# DIB_Top_Sheet.net
KiCad netlist of a schematic drawn in Altium Designer
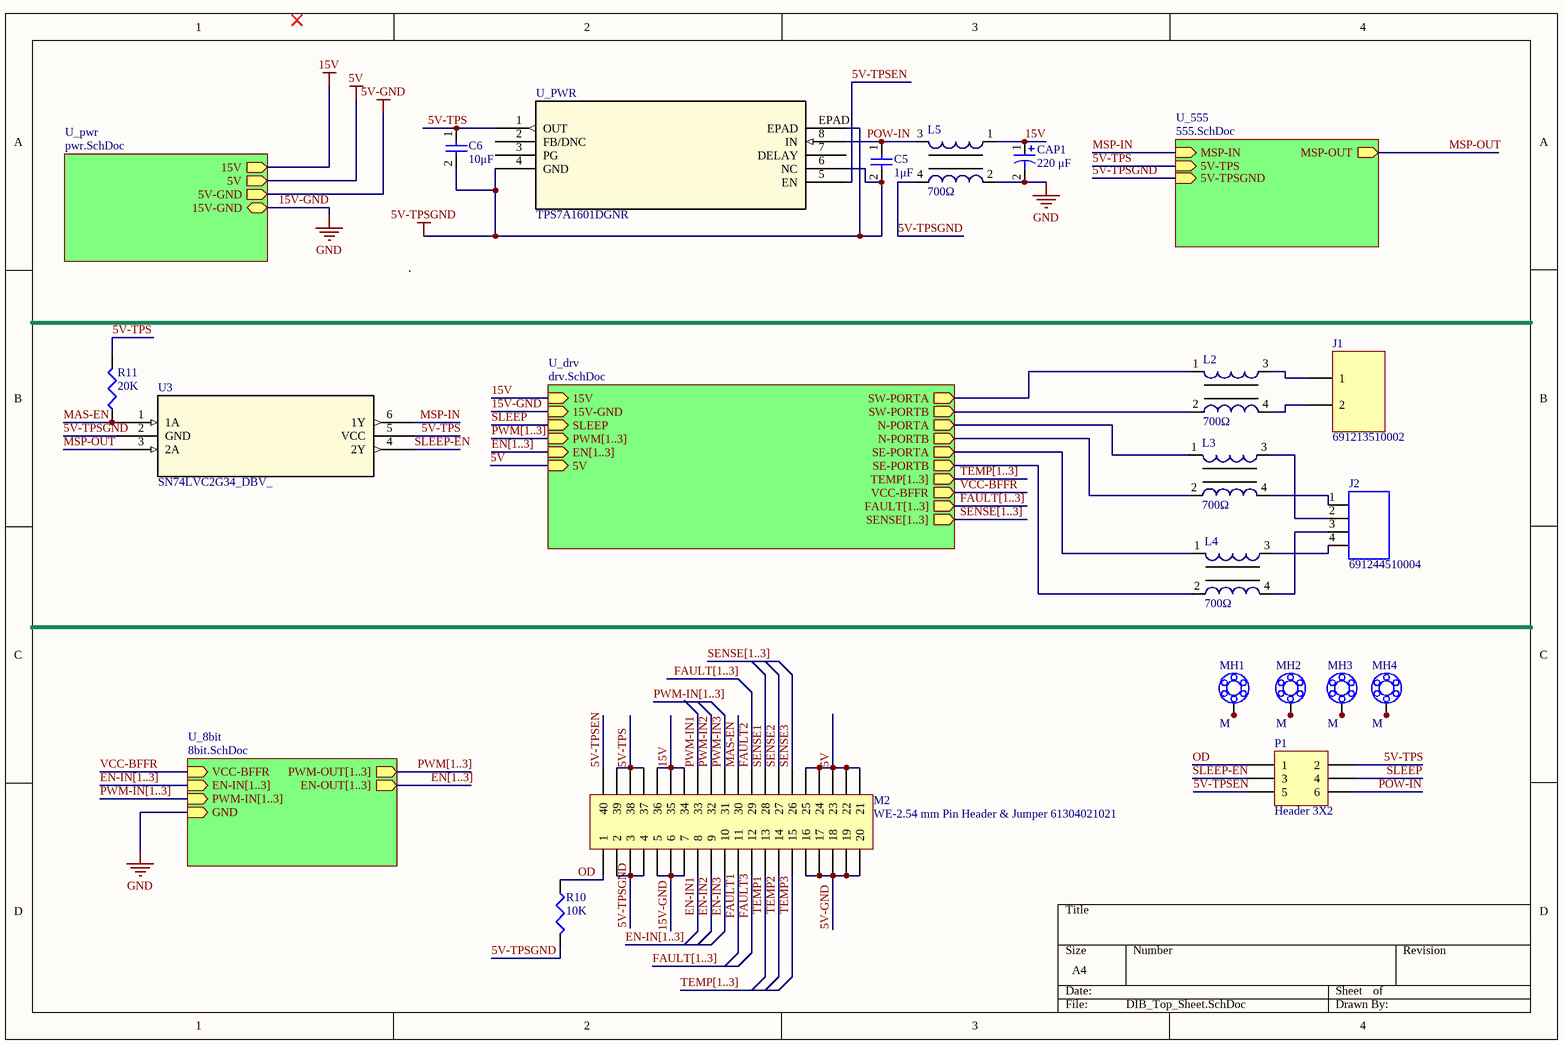
[diagram p0: DIB_Top_Sheet.SchDoc]

(export (version "E")
  (design (tool "Eeschema 10.0.6"))
  (components
    (comp (ref "C5")
      (value "1μF")
      (footprint "WCAP-CSGP 0805, H=1.25mm")
      (description "CAP CER 1UF 50V 10% X5R 0805")
      (fields
        (field (name "MANUFACTURER") "TDK")
        (field (name "PARTNO") "CGA4J3X5R1H105K125AB (C6)")
        (field (name "CREATED BY") "Saurabh")
      )
      (libsource (lib "WCAP-CSGP_rev15b") (part "WCAP-CSGP 0805, 885012207026"))
    )
    (comp (ref "C6")
      (value "10μF")
      (footprint "WCAP-CSGP 0805, H=1.25mm")
      (description "CAP CER 10UF 6.3V 10% X7R 0805")
      (fields
        (field (name "MANUFACTURER") "TDK")
        (field (name "PARTNO") "CGJ4J1X7R0J106K125AC")
        (field (name "CREATED BY") "Saurabh")
      )
      (libsource (lib "WCAP-CSGP_rev15b") (part "WCAP-CSGP 0805, 885012207026"))
    )
    (comp (ref "CAP1")
      (value "220 μF")
      (footprint "WCAP-ASLL 10x10.5x4.5")
      (description "WCAP-ASLL Aluminum Electrolytic Capacitors , 220 μF; + / - 20%; 35 V , 10 x 10,5")
      (fields
        (field (name "MANUFACTURER") "Wurth Elektronik")
        (field (name "PARTNO") "865060557008")
        (field (name "E-MAIL") "libraries@we-online.com")
        (field (name "CREATED BY") "Karrer Zheng")
      )
      (libsource (lib "WCAP-ASLL_rev15a") (part "WCAP-ASLL 10x10.5x4.5 865060557008"))
    )
    (comp (ref "J1")
      (value "691213510002")
      (footprint "691213510002")
      (description "Horizontal Cable Entry with Rising Cage Clamp, Serie 2135 - 5.08 mm")
      (fields (field (name "MANUFACTURER") "Wurth Elektronik") (field (name "CREATED BY") "Baojun Chen"))
      (libsource (lib "WE_WR-TBL_Rising Cage System_5.08 mm_rev15b") (part "691213510002"))
    )
    (comp (ref "J2")
      (value "691244510004")
      (footprint "691244510004")
      (description "WR-TBL Horizontal Cable Entry With Rising Cage Clamp,Serie 2445 - 5.08 mm")
      (fields (field (name "MANUFACTURER") "Wurth Elektronik") (field (name "CREATED BY") "Baojun Chen"))
      (libsource (lib "WE_WR-TBL_Rising Cage System_5.08 mm_rev15b") (part "691244510004"))
    )
    (comp (ref "L2")
      (value "700Ω")
      (footprint "IND_TDK_ACM70600")
      (description "ACM7060-701-2PL-TL01")
      (fields (field (name "MANUFACTURER") "TDK") (field (name "CREATED BY") "Saurabh Sharma"))
      (libsource (lib "WE-SCC_rev15a") (part "WE-SCC 7345, 744281100"))
    )
    (comp (ref "L3")
      (value "700Ω")
      (footprint "IND_TDK_ACM70600")
      (description "ACM7060-701-2PL-TL01")
      (fields (field (name "MANUFACTURER") "TDK") (field (name "CREATED BY") "Saurabh Sharma"))
      (libsource (lib "WE-SCC_rev15a") (part "WE-SCC 7345, 744281100"))
    )
    (comp (ref "L4")
      (value "700Ω")
      (footprint "IND_TDK_ACM70600")
      (description "ACM7060-701-2PL-TL01")
      (fields (field (name "MANUFACTURER") "TDK") (field (name "CREATED BY") "Saurabh Sharma"))
      (libsource (lib "WE-SCC_rev15a") (part "WE-SCC 7345, 744281100"))
    )
    (comp (ref "L5")
      (value "700Ω")
      (footprint "IND_TDK_ACM70600")
      (description "ACM7060-701-2PL-TL01")
      (fields (field (name "MANUFACTURER") "TDK") (field (name "CREATED BY") "Saurabh Sharma"))
      (libsource (lib "") (part "WE-SCC 7345, 744281100_1"))
    )
    (comp (ref "M2")
      (value "WE-2.54 mm Pin Header & Jumper 61304021021")
      (footprint "61304021021")
      (description "WR-PHD 2.54 mm Angled Dual Pin Header")
      (fields
        (field (name "MANUFACTURER") "Würth Elektronik eiSos GmbH")
        (field (name "PARTNO") "61304021021")
        (field (name "CREATED BY") "Karrer Zheng")
      )
      (libsource (lib "WE_WR-PHD_Pin Header_2.54mm_rev15c") (part "WE-2.54 mm Pin Header & Jumper 61304021021"))
    )
    (comp (ref "MH1")
      (value "M")
      (footprint "MOUNTING")
      (description "MOUNTING HOLE - NON INSTALLABLE")
      (libsource (lib "vh_altium_library") (part "MOUNTING"))
    )
    (comp (ref "MH2")
      (value "M")
      (footprint "MOUNTING")
      (description "MOUNTING HOLE - NON INSTALLABLE")
      (libsource (lib "vh_altium_library") (part "MOUNTING"))
    )
    (comp (ref "MH3")
      (value "M")
      (footprint "MOUNTING")
      (description "MOUNTING HOLE - NON INSTALLABLE")
      (libsource (lib "vh_altium_library") (part "MOUNTING"))
    )
    (comp (ref "MH4")
      (value "M")
      (footprint "MOUNTING")
      (description "MOUNTING HOLE - NON INSTALLABLE")
      (libsource (lib "vh_altium_library") (part "MOUNTING"))
    )
    (comp (ref "P1")
      (value "Header 3X2")
      (footprint "HDR2X3")
      (description "Header, 3-Pin, Dual row")
      (fields (field (name "PUBLISHER") "Altium Limited"))
      (libsource (lib "Miscellaneous Connectors") (part "Header 3X2"))
    )
    (comp (ref "R10")
      (value "10K")
      (footprint "J1-0603")
      (description "Resistor")
      (fields (field (name "PUBLISHER") "Altium Limited"))
      (libsource (lib "Miscellaneous Devices") (part "Res3"))
    )
    (comp (ref "R11")
      (value "20K")
      (footprint "J1-0603")
      (description "Resistor")
      (fields (field (name "PUBLISHER") "Altium Limited"))
      (libsource (lib "Miscellaneous Devices") (part "Res3"))
    )
    (comp (ref "U3")
      (value "SN74LVC2G34_DBV_")
      (footprint "DBV6")
      (description "Imported")
      (fields
        (field (name "MANUFACTURER") "Texas Instruments")
        (field (name "GENERIC_PART_NUMBER") "SN74LVC2G34")
      )
      (libsource (lib "2016-10-29_23-31-42") (part "SN74LVC2G34_DBV_"))
    )
    (comp (ref "U_PWR")
      (value "TPS7A1601DGNR")
      (footprint "DGN8_1P92X1P6")
      (description "Imported")
      (fields
        (field (name "GENERIC_PART_NUMBER") "TPS7A1601")
        (field (name "MANUFACTURER") "Texas Instruments")
        (field (name "COPYRIGHT") "Copyright (C) 2015 Accelerated Designs. All rights reserved")
      )
      (libsource (lib "TPS7A16") (part "TPS7A1601DGNR"))
    )
  )
  (nets
    (net (code "7") (name "/5V-TPS") (class "Default")
      (node (ref "C6") (pin "1") (pinfunction "1_1") (pintype "passive"))
      (node (ref "M2") (pin "37") (pinfunction "37_37") (pintype "passive"))
      (node (ref "M2") (pin "38") (pinfunction "38_38") (pintype "passive"))
      (node (ref "M2") (pin "39") (pinfunction "39_39") (pintype "passive"))
      (node (ref "P1") (pin "2") (pinfunction "2_2") (pintype "passive"))
      (node (ref "R11") (pin "2") (pinfunction "2_2") (pintype "passive"))
      (node (ref "U3") (pin "5") (pinfunction "VCC_5") (pintype "power_in"))
      (node (ref "U_PWR") (pin "1") (pinfunction "OUT_1") (pintype "output"))
    )
    (net (code "8") (name "/5V-TPSEN") (class "Default")
      (node (ref "M2") (pin "40") (pinfunction "40_40") (pintype "passive"))
      (node (ref "P1") (pin "5") (pinfunction "5_5") (pintype "passive"))
      (node (ref "U_PWR") (pin "5") (pinfunction "EN_5") (pintype "passive"))
    )
    (net (code "9") (name "/EN-IN1") (class "Default")
      (node (ref "M2") (pin "8") (pinfunction "8_8") (pintype "passive"))
    )
    (net (code "10") (name "/EN-IN2") (class "Default")
      (node (ref "M2") (pin "9") (pinfunction "9_9") (pintype "passive"))
    )
    (net (code "11") (name "/EN-IN3") (class "Default")
      (node (ref "M2") (pin "10") (pinfunction "10_10") (pintype "passive"))
    )
    (net (code "14") (name "/FAULT1") (class "Default")
      (node (ref "M2") (pin "11") (pinfunction "11_11") (pintype "passive"))
    )
    (net (code "15") (name "/FAULT2") (class "Default")
      (node (ref "M2") (pin "29") (pinfunction "29_29") (pintype "passive"))
    )
    (net (code "16") (name "/FAULT3") (class "Default")
      (node (ref "M2") (pin "12") (pinfunction "12_12") (pintype "passive"))
    )
    (net (code "18") (name "/MAS-EN") (class "Default")
      (node (ref "M2") (pin "30") (pinfunction "30_30") (pintype "passive"))
      (node (ref "R11") (pin "1") (pinfunction "1_1") (pintype "passive"))
      (node (ref "U3") (pin "1") (pinfunction "1A_1") (pintype "input"))
    )
    (net (code "19") (name "/MSP-IN") (class "Default")
      (node (ref "U3") (pin "6") (pinfunction "1Y_6") (pintype "output"))
    )
    (net (code "20") (name "/MSP-OUT") (class "Default")
      (node (ref "U3") (pin "3") (pinfunction "2A_3") (pintype "input"))
    )
    (net (code "21") (name "/N-PORTA") (class "Default")
      (node (ref "L3") (pin "1") (pinfunction "1_1") (pintype "passive"))
    )
    (net (code "22") (name "/N-PORTB") (class "Default")
      (node (ref "L3") (pin "2") (pinfunction "2_2") (pintype "passive"))
    )
    (net (code "23") (name "/OD") (class "Default")
      (node (ref "M2") (pin "1") (pinfunction "1_1") (pintype "passive"))
      (node (ref "P1") (pin "1") (pinfunction "1_1") (pintype "passive"))
      (node (ref "R10") (pin "2") (pinfunction "2_2") (pintype "passive"))
    )
    (net (code "24") (name "/POW-IN") (class "Default")
      (node (ref "C5") (pin "1") (pinfunction "1_1") (pintype "passive"))
      (node (ref "L5") (pin "3") (pinfunction "3_3") (pintype "passive"))
      (node (ref "P1") (pin "6") (pinfunction "6_6") (pintype "passive"))
      (node (ref "U_PWR") (pin "8") (pinfunction "IN_8") (pintype "input"))
    )
    (net (code "25") (name "/PWM-IN1") (class "Default")
      (node (ref "M2") (pin "33") (pinfunction "33_33") (pintype "passive"))
    )
    (net (code "26") (name "/PWM-IN2") (class "Default")
      (node (ref "M2") (pin "32") (pinfunction "32_32") (pintype "passive"))
    )
    (net (code "27") (name "/PWM-IN3") (class "Default")
      (node (ref "M2") (pin "31") (pinfunction "31_31") (pintype "passive"))
    )
    (net (code "30") (name "/SE-PORTA") (class "Default")
      (node (ref "L4") (pin "1") (pinfunction "1_1") (pintype "passive"))
    )
    (net (code "31") (name "/SE-PORTB") (class "Default")
      (node (ref "L4") (pin "2") (pinfunction "2_2") (pintype "passive"))
    )
    (net (code "32") (name "/SENSE1") (class "Default")
      (node (ref "M2") (pin "28") (pinfunction "28_28") (pintype "passive"))
    )
    (net (code "33") (name "/SENSE2") (class "Default")
      (node (ref "M2") (pin "27") (pinfunction "27_27") (pintype "passive"))
    )
    (net (code "34") (name "/SENSE3") (class "Default")
      (node (ref "M2") (pin "26") (pinfunction "26_26") (pintype "passive"))
    )
    (net (code "36") (name "/SLEEP") (class "Default")
      (node (ref "P1") (pin "4") (pinfunction "4_4") (pintype "passive"))
    )
    (net (code "37") (name "/SLEEP-EN") (class "Default")
      (node (ref "P1") (pin "3") (pinfunction "3_3") (pintype "passive"))
      (node (ref "U3") (pin "4") (pinfunction "2Y_4") (pintype "output"))
    )
    (net (code "38") (name "/SW-PORTA") (class "Default")
      (node (ref "L2") (pin "1") (pinfunction "1_1") (pintype "passive"))
    )
    (net (code "39") (name "/SW-PORTB") (class "Default")
      (node (ref "L2") (pin "2") (pinfunction "2_2") (pintype "passive"))
    )
    (net (code "40") (name "/TEMP1") (class "Default")
      (node (ref "M2") (pin "13") (pinfunction "13_13") (pintype "passive"))
    )
    (net (code "41") (name "/TEMP2") (class "Default")
      (node (ref "M2") (pin "14") (pinfunction "14_14") (pintype "passive"))
    )
    (net (code "42") (name "/TEMP3") (class "Default")
      (node (ref "M2") (pin "15") (pinfunction "15_15") (pintype "passive"))
    )
    (net (code "45") (name "5V") (class "Default")
      (node (ref "M2") (pin "21") (pinfunction "21_21") (pintype "passive"))
      (node (ref "M2") (pin "22") (pinfunction "22_22") (pintype "passive"))
      (node (ref "M2") (pin "23") (pinfunction "23_23") (pintype "passive"))
      (node (ref "M2") (pin "24") (pinfunction "24_24") (pintype "passive"))
      (node (ref "M2") (pin "25") (pinfunction "25_25") (pintype "passive"))
    )
    (net (code "46") (name "5V-GND") (class "Default")
      (node (ref "M2") (pin "16") (pinfunction "16_16") (pintype "passive"))
      (node (ref "M2") (pin "17") (pinfunction "17_17") (pintype "passive"))
      (node (ref "M2") (pin "18") (pinfunction "18_18") (pintype "passive"))
      (node (ref "M2") (pin "19") (pinfunction "19_19") (pintype "passive"))
      (node (ref "M2") (pin "20") (pinfunction "20_20") (pintype "passive"))
    )
    (net (code "47") (name "5V-TPSGND") (class "Default")
      (node (ref "C5") (pin "2") (pinfunction "2_2") (pintype "passive"))
      (node (ref "C6") (pin "2") (pinfunction "2_2") (pintype "passive"))
      (node (ref "L5") (pin "4") (pinfunction "4_4") (pintype "passive"))
      (node (ref "M2") (pin "2") (pinfunction "2_2") (pintype "passive"))
      (node (ref "M2") (pin "3") (pinfunction "3_3") (pintype "passive"))
      (node (ref "M2") (pin "4") (pinfunction "4_4") (pintype "passive"))
      (node (ref "R10") (pin "1") (pinfunction "1_1") (pintype "passive"))
      (node (ref "U3") (pin "2") (pinfunction "GND_2") (pintype "power_in"))
      (node (ref "U_PWR") (pin "4") (pinfunction "GND_4") (pintype "power_in"))
      (node (ref "U_PWR") (pin "6") (pinfunction "NC_6") (pintype "passive"))
      (node (ref "U_PWR") (pin "EPAD") (pinfunction "EPAD_EPAD") (pintype "passive"))
    )
    (net (code "48") (name "15V") (class "Default")
      (node (ref "CAP1") (pin "1") (pinfunction "1_1") (pintype "passive"))
      (node (ref "L5") (pin "1") (pinfunction "1_1") (pintype "passive"))
      (node (ref "M2") (pin "34") (pinfunction "34_34") (pintype "passive"))
      (node (ref "M2") (pin "35") (pinfunction "35_35") (pintype "passive"))
      (node (ref "M2") (pin "36") (pinfunction "36_36") (pintype "passive"))
    )
    (net (code "49") (name "GND") (class "Default")
      (node (ref "CAP1") (pin "2") (pinfunction "2_2") (pintype "passive"))
      (node (ref "L5") (pin "2") (pinfunction "2_2") (pintype "passive"))
      (node (ref "M2") (pin "5") (pinfunction "5_5") (pintype "passive"))
      (node (ref "M2") (pin "6") (pinfunction "6_6") (pintype "passive"))
      (node (ref "M2") (pin "7") (pinfunction "7_7") (pintype "passive"))
    )
    (net (code "50") (name "Net-(J1-Pad1)") (class "Default")
      (node (ref "J1") (pin "1") (pinfunction "1_1") (pintype "passive"))
      (node (ref "L2") (pin "3") (pinfunction "3_3") (pintype "passive"))
    )
    (net (code "51") (name "Net-(J1-Pad2)") (class "Default")
      (node (ref "J1") (pin "2") (pinfunction "2_2") (pintype "passive"))
      (node (ref "L2") (pin "4") (pinfunction "4_4") (pintype "passive"))
    )
    (net (code "52") (name "Net-(J2-Pad1)") (class "Default")
      (node (ref "J2") (pin "1") (pinfunction "1_1") (pintype "passive"))
      (node (ref "L3") (pin "4") (pinfunction "4_4") (pintype "passive"))
    )
    (net (code "53") (name "Net-(J2-Pad2)") (class "Default")
      (node (ref "J2") (pin "2") (pinfunction "2_2") (pintype "passive"))
      (node (ref "L3") (pin "3") (pinfunction "3_3") (pintype "passive"))
    )
    (net (code "54") (name "Net-(J2-Pad3)") (class "Default")
      (node (ref "J2") (pin "3") (pinfunction "3_3") (pintype "passive"))
      (node (ref "L4") (pin "4") (pinfunction "4_4") (pintype "passive"))
    )
    (net (code "55") (name "Net-(J2-Pad4)") (class "Default")
      (node (ref "J2") (pin "4") (pinfunction "4_4") (pintype "passive"))
      (node (ref "L4") (pin "3") (pinfunction "3_3") (pintype "passive"))
    )
    (net (code "56") (name "Net-(MH1-Pad1)") (class "Default")
      (node (ref "MH1") (pin "1") (pinfunction "1_1") (pintype "passive"))
      (node (ref "MH1") (pin "2") (pinfunction "2_2") (pintype "passive"))
      (node (ref "MH1") (pin "3") (pinfunction "3_3") (pintype "passive"))
      (node (ref "MH1") (pin "4") (pinfunction "4_4") (pintype "passive"))
      (node (ref "MH1") (pin "5") (pinfunction "5_5") (pintype "passive"))
      (node (ref "MH1") (pin "6") (pinfunction "6_6") (pintype "passive"))
      (node (ref "MH1") (pin "7") (pinfunction "7_7") (pintype "passive"))
      (node (ref "MH1") (pin "8") (pinfunction "8_8") (pintype "passive"))
      (node (ref "MH1") (pin "9") (pinfunction "9_9") (pintype "passive"))
    )
    (net (code "57") (name "Net-(MH2-Pad1)") (class "Default")
      (node (ref "MH2") (pin "1") (pinfunction "1_1") (pintype "passive"))
      (node (ref "MH2") (pin "2") (pinfunction "2_2") (pintype "passive"))
      (node (ref "MH2") (pin "3") (pinfunction "3_3") (pintype "passive"))
      (node (ref "MH2") (pin "4") (pinfunction "4_4") (pintype "passive"))
      (node (ref "MH2") (pin "5") (pinfunction "5_5") (pintype "passive"))
      (node (ref "MH2") (pin "6") (pinfunction "6_6") (pintype "passive"))
      (node (ref "MH2") (pin "7") (pinfunction "7_7") (pintype "passive"))
      (node (ref "MH2") (pin "8") (pinfunction "8_8") (pintype "passive"))
      (node (ref "MH2") (pin "9") (pinfunction "9_9") (pintype "passive"))
    )
    (net (code "58") (name "Net-(MH3-Pad1)") (class "Default")
      (node (ref "MH3") (pin "1") (pinfunction "1_1") (pintype "passive"))
      (node (ref "MH3") (pin "2") (pinfunction "2_2") (pintype "passive"))
      (node (ref "MH3") (pin "3") (pinfunction "3_3") (pintype "passive"))
      (node (ref "MH3") (pin "4") (pinfunction "4_4") (pintype "passive"))
      (node (ref "MH3") (pin "5") (pinfunction "5_5") (pintype "passive"))
      (node (ref "MH3") (pin "6") (pinfunction "6_6") (pintype "passive"))
      (node (ref "MH3") (pin "7") (pinfunction "7_7") (pintype "passive"))
      (node (ref "MH3") (pin "8") (pinfunction "8_8") (pintype "passive"))
      (node (ref "MH3") (pin "9") (pinfunction "9_9") (pintype "passive"))
    )
    (net (code "59") (name "Net-(MH4-Pad1)") (class "Default")
      (node (ref "MH4") (pin "1") (pinfunction "1_1") (pintype "passive"))
      (node (ref "MH4") (pin "2") (pinfunction "2_2") (pintype "passive"))
      (node (ref "MH4") (pin "3") (pinfunction "3_3") (pintype "passive"))
      (node (ref "MH4") (pin "4") (pinfunction "4_4") (pintype "passive"))
      (node (ref "MH4") (pin "5") (pinfunction "5_5") (pintype "passive"))
      (node (ref "MH4") (pin "6") (pinfunction "6_6") (pintype "passive"))
      (node (ref "MH4") (pin "7") (pinfunction "7_7") (pintype "passive"))
      (node (ref "MH4") (pin "8") (pinfunction "8_8") (pintype "passive"))
      (node (ref "MH4") (pin "9") (pinfunction "9_9") (pintype "passive"))
    )
    (net (code "60") (name "unconnected-(U_PWR-DELAY-Pad7)") (class "Default")
      (node (ref "U_PWR") (pin "7") (pinfunction "DELAY_7") (pintype "passive"))
    )
    (net (code "61") (name "unconnected-(U_PWR-FB{slash}DNC-Pad2)") (class "Default")
      (node (ref "U_PWR") (pin "2") (pinfunction "FB/DNC_2") (pintype "passive"))
    )
    (net (code "62") (name "unconnected-(U_PWR-PG-Pad3)") (class "Default")
      (node (ref "U_PWR") (pin "3") (pinfunction "PG_3") (pintype "passive"))
    )
  )
)
